# PM12_P1V8.net
KiCad netlist of a schematic drawn in Altium Designer
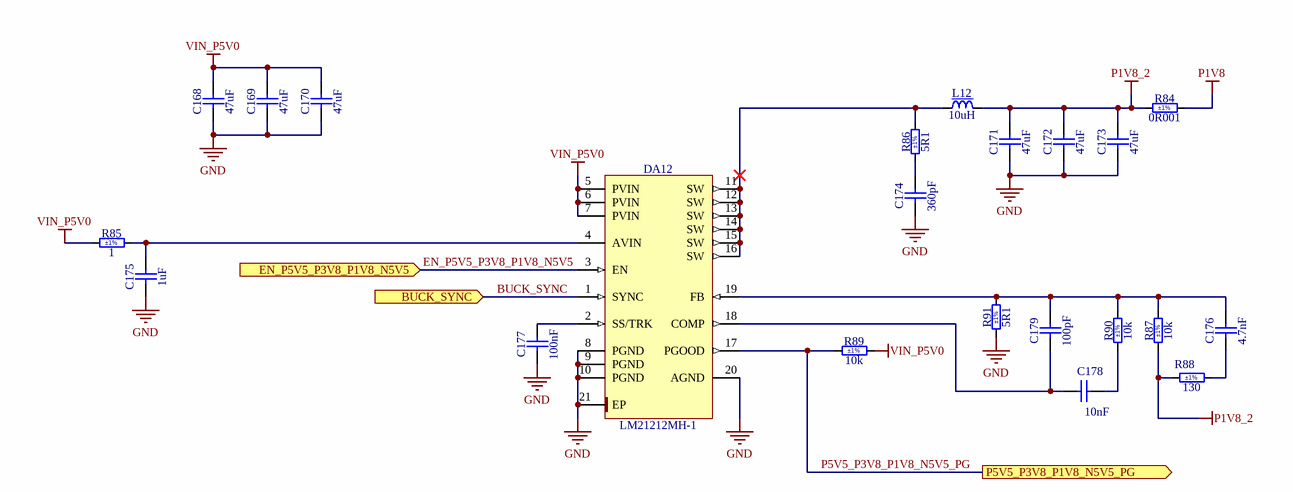
[diagram p0: PM12_P1V8.SchDoc]

(export (version "E")
  (design (tool "Eeschema 10.0.6"))
  (components
    (comp (ref "C168")
      (value "47uF")
      (footprint "CAPC3225X270N")
      (description "Non-polarised capacitor")
      (fields
        (field (name "PART NUMBER") "CC1210_47UF_16V_20%_X5R")
        (field (name "VOLTAGE") "16V")
        (field (name "AUTHOR") "CERN DEM MR")
      )
      (libsource (lib "Capacitors") (part "Capacitor - non polarized"))
    )
    (comp (ref "C169")
      (value "47uF")
      (footprint "CAPC3225X270N")
      (description "Non-polarised capacitor")
      (fields
        (field (name "PART NUMBER") "CC1210_47UF_16V_20%_X5R")
        (field (name "VOLTAGE") "16V")
        (field (name "AUTHOR") "CERN DEM MR")
      )
      (libsource (lib "Capacitors") (part "Capacitor - non polarized"))
    )
    (comp (ref "C170")
      (value "47uF")
      (footprint "CAPC3225X270N")
      (description "Non-polarised capacitor")
      (fields
        (field (name "PART NUMBER") "CC1210_47UF_16V_20%_X5R")
        (field (name "VOLTAGE") "16V")
        (field (name "AUTHOR") "CERN DEM MR")
      )
      (libsource (lib "Capacitors") (part "Capacitor - non polarized"))
    )
    (comp (ref "C171")
      (value "47uF")
      (footprint "CAPC3225X270N")
      (description "Non-polarised capacitor")
      (fields
        (field (name "PART NUMBER") "CC1210_47UF_16V_20%_X5R")
        (field (name "VOLTAGE") "16V")
        (field (name "AUTHOR") "CERN DEM MR")
      )
      (libsource (lib "Capacitors") (part "Capacitor - non polarized"))
    )
    (comp (ref "C172")
      (value "47uF")
      (footprint "CAPC3225X270N")
      (description "Non-polarised capacitor")
      (fields
        (field (name "PART NUMBER") "CC1210_47UF_16V_20%_X5R")
        (field (name "VOLTAGE") "16V")
        (field (name "AUTHOR") "CERN DEM MR")
      )
      (libsource (lib "Capacitors") (part "Capacitor - non polarized"))
    )
    (comp (ref "C173")
      (value "47uF")
      (footprint "CAPC3225X270N")
      (description "Non-polarised capacitor")
      (fields
        (field (name "PART NUMBER") "CC1210_47UF_16V_20%_X5R")
        (field (name "VOLTAGE") "16V")
        (field (name "AUTHOR") "CERN DEM MR")
      )
      (libsource (lib "Capacitors") (part "Capacitor - non polarized"))
    )
    (comp (ref "C174")
      (value "360pF")
      (footprint "CAPC2013X145N")
      (description "Non-polarised capacitor")
      (fields
        (field (name "PART NUMBER") "CC0805_360PF_50V_5%_C0G")
        (field (name "VOLTAGE") "50V")
        (field (name "AUTHOR") "CERN DEM HF")
      )
      (libsource (lib "Capacitors") (part "Capacitor - non polarized"))
    )
    (comp (ref "C175")
      (value "1uF")
      (footprint "CAPC2012X140N")
      (description "Non-polarised capacitor")
      (fields
        (field (name "PART NUMBER") "CC0805_1UF_25V_10%_X7R")
        (field (name "VOLTAGE") "25V")
        (field (name "AUTHOR") "CERN DEM JLC")
      )
      (libsource (lib "Capacitors") (part "Capacitor - non polarized"))
    )
    (comp (ref "C176")
      (value "4.7nF")
      (footprint "CAPC2012X135N")
      (description "Non-polarised capacitor")
      (fields
        (field (name "PART NUMBER") "CC0805_4.7NF_50V_10%_X7R")
        (field (name "VOLTAGE") "50V")
        (field (name "AUTHOR") "CERN DEM JLC")
      )
      (libsource (lib "Capacitors") (part "Capacitor - non polarized"))
    )
    (comp (ref "C177")
      (value "100nF")
      (footprint "CAPC2012X135N")
      (description "Non-polarised capacitor")
      (fields
        (field (name "PART NUMBER") "CC0805_100NF_50V_10%_X7R")
        (field (name "VOLTAGE") "50V")
        (field (name "AUTHOR") "CERN DEM JLC")
      )
      (libsource (lib "Capacitors") (part "Capacitor - non polarized"))
    )
    (comp (ref "C178")
      (value "10nF")
      (footprint "CAPC1005X55N")
      (description "Non-polarised capacitor")
      (fields
        (field (name "PART NUMBER") "CC0402_10NF_25V_10%_X7R")
        (field (name "VOLTAGE") "25V")
        (field (name "AUTHOR") "CERN DEM JLC")
      )
      (libsource (lib "Capacitors") (part "Capacitor - non polarized"))
    )
    (comp (ref "C179")
      (value "100pF")
      (footprint "CAPC2012X135N")
      (description "Non-polarised capacitor")
      (fields
        (field (name "PART NUMBER") "CC0805_100PF_50V_5%_NP0")
        (field (name "VOLTAGE") "50V")
        (field (name "AUTHOR") "CERN DEM JLC")
      )
      (libsource (lib "Capacitors") (part "Capacitor - non polarized"))
    )
    (comp (ref "DA12")
      (value "LM21212MH-1")
      (footprint "TEXAS_PWP0020AA")
      (description "2.95-V To 5.5-V, 12-A, Voltage-Mode Synchronous Buck Regulator with Frequency Synchronization")
      (fields (field (name "MANUFACTURER") "TEXAS INSTRUMENTS") (field (name "AUTHOR") "CERN DEM HF"))
      (libsource (lib "ICs And Semiconductors") (part "LM21212"))
    )
    (comp (ref "L12")
      (value "10uH")
      (footprint "IND_VISHAY_IHPL4040DZ-01")
      (description "Inductor With Core")
      (fields
        (field (name "PART NUMBER") "IND4040_10UH_20%_VISHAY_IHLP-4040DZ-01")
        (field (name "POWER") "6.8A")
        (field (name "AUTHOR") "CERN DEM HF")
      )
      (libsource (lib "Inductors & Transformers") (part "Inductor With Magnetic core"))
    )
    (comp (ref "R84")
      (value "0R001")
      (footprint "RESC_BOURNS_CRE2512_0R001-0R004")
      (description "Resistor - 1%")
      (fields
        (field (name "TOLERANCE") "±1%")
        (field (name "PART NUMBER") "R2512_0R001_1%_3W_50PPM_BOURNS_CRE2512")
        (field (name "POWER") "3W")
        (field (name "AUTHOR") "CERN DEM BC")
      )
      (libsource (lib "Resistors") (part "Resistor - 1%"))
    )
    (comp (ref "R85")
      (value "1")
      (footprint "RESC2012X60N")
      (description "Resistor - 1%")
      (fields
        (field (name "TOLERANCE") "±1%")
        (field (name "PART NUMBER") "R0805_1R_1%_0.125W_100PPM")
        (field (name "POWER") "0.125W")
        (field (name "AUTHOR") "CERN DEM HF")
      )
      (libsource (lib "Resistors") (part "Resistor - 1%"))
    )
    (comp (ref "R86")
      (value "5R1")
      (footprint "RESC2012X60N")
      (description "Resistor - 1%")
      (fields
        (field (name "TOLERANCE") "±1%")
        (field (name "PART NUMBER") "R0805_5R1_1%_0.125W_100PPM")
        (field (name "POWER") "0.125W")
        (field (name "AUTHOR") "CERN DEM HF")
      )
      (libsource (lib "Resistors") (part "Resistor - 1%"))
    )
    (comp (ref "R87")
      (value "10k")
      (footprint "RESC1608X55N")
      (description "Resistor - 1%")
      (fields
        (field (name "TOLERANCE") "±1%")
        (field (name "PART NUMBER") "R0603_10K_1%_0.1W_100PPM")
        (field (name "POWER") "0.1W")
        (field (name "AUTHOR") "CERN DEM JLC")
      )
      (libsource (lib "Resistors") (part "Resistor - 1%"))
    )
    (comp (ref "R88")
      (value "130")
      (footprint "RESC2012X60N")
      (description "Resistor - 1%")
      (fields
        (field (name "TOLERANCE") "±1%")
        (field (name "PART NUMBER") "R0805_130R_1%_0.125W_100PPM")
        (field (name "POWER") "0.125W")
        (field (name "AUTHOR") "CERN DEM JLC")
      )
      (libsource (lib "Resistors") (part "Resistor - 1%"))
    )
    (comp (ref "R89")
      (value "10k")
      (footprint "RESC1608X55N")
      (description "Resistor - 1%")
      (fields
        (field (name "TOLERANCE") "±1%")
        (field (name "PART NUMBER") "R0603_10K_1%_0.1W_100PPM")
        (field (name "POWER") "0.1W")
        (field (name "AUTHOR") "CERN DEM JLC")
      )
      (libsource (lib "Resistors") (part "Resistor - 1%"))
    )
    (comp (ref "R90")
      (value "10k")
      (footprint "RESC1608X55N")
      (description "Resistor - 1%")
      (fields
        (field (name "TOLERANCE") "±1%")
        (field (name "PART NUMBER") "R0603_10K_1%_0.1W_100PPM")
        (field (name "POWER") "0.1W")
        (field (name "AUTHOR") "CERN DEM JLC")
      )
      (libsource (lib "Resistors") (part "Resistor - 1%"))
    )
    (comp (ref "R91")
      (value "5R1")
      (footprint "RESC2012X60N")
      (description "Resistor - 1%")
      (fields
        (field (name "TOLERANCE") "±1%")
        (field (name "PART NUMBER") "R0805_5R1_1%_0.125W_100PPM")
        (field (name "POWER") "0.125W")
        (field (name "AUTHOR") "CERN DEM HF")
      )
      (libsource (lib "Resistors") (part "Resistor - 1%"))
    )
  )
  (nets
    (net (code "1") (name "/BUCK_SYNC") (class "Default")
      (node (ref "DA12") (pin "1") (pinfunction "SYNC_1") (pintype "input"))
    )
    (net (code "2") (name "/EN_P5V5_P3V8_P1V8_N5V5") (class "Default")
      (node (ref "DA12") (pin "3") (pinfunction "EN_3") (pintype "input"))
    )
    (net (code "3") (name "/P5V5_P3V8_P1V8_N5V5_PG") (class "Default")
      (node (ref "DA12") (pin "17") (pinfunction "PGOOD_17") (pintype "output"))
      (node (ref "R89") (pin "1") (pinfunction "1_1") (pintype "passive"))
    )
    (net (code "4") (name "GND") (class "Default")
      (node (ref "C168") (pin "1") (pinfunction "1_1") (pintype "passive"))
      (node (ref "C169") (pin "1") (pinfunction "1_1") (pintype "passive"))
      (node (ref "C170") (pin "1") (pinfunction "1_1") (pintype "passive"))
      (node (ref "C171") (pin "1") (pinfunction "1_1") (pintype "passive"))
      (node (ref "C172") (pin "1") (pinfunction "1_1") (pintype "passive"))
      (node (ref "C173") (pin "1") (pinfunction "1_1") (pintype "passive"))
      (node (ref "C174") (pin "1") (pinfunction "1_1") (pintype "passive"))
      (node (ref "C175") (pin "1") (pinfunction "1_1") (pintype "passive"))
      (node (ref "C177") (pin "1") (pinfunction "1_1") (pintype "passive"))
      (node (ref "DA12") (pin "10") (pinfunction "PGND_10") (pintype "power_in"))
      (node (ref "DA12") (pin "20") (pinfunction "AGND_20") (pintype "power_in"))
      (node (ref "DA12") (pin "21") (pinfunction "EP_21") (pintype "power_in"))
      (node (ref "DA12") (pin "8") (pinfunction "PGND_8") (pintype "power_in"))
      (node (ref "DA12") (pin "9") (pinfunction "PGND_9") (pintype "power_in"))
      (node (ref "R91") (pin "1") (pinfunction "1_1") (pintype "passive"))
    )
    (net (code "5") (name "Net-(C174-Pad2)") (class "Default")
      (node (ref "C174") (pin "2") (pinfunction "2_2") (pintype "passive"))
      (node (ref "R86") (pin "1") (pinfunction "1_1") (pintype "passive"))
    )
    (net (code "6") (name "Net-(C176-Pad1)") (class "Default")
      (node (ref "C176") (pin "1") (pinfunction "1_1") (pintype "passive"))
      (node (ref "R88") (pin "1") (pinfunction "1_1") (pintype "passive"))
    )
    (net (code "7") (name "Net-(C178-Pad1)") (class "Default")
      (node (ref "C178") (pin "1") (pinfunction "1_1") (pintype "passive"))
      (node (ref "R90") (pin "1") (pinfunction "1_1") (pintype "passive"))
    )
    (net (code "8") (name "Net-(DA12-AVIN)") (class "Default")
      (node (ref "C175") (pin "2") (pinfunction "2_2") (pintype "passive"))
      (node (ref "DA12") (pin "4") (pinfunction "AVIN_4") (pintype "power_in"))
      (node (ref "R85") (pin "2") (pinfunction "2_2") (pintype "passive"))
    )
    (net (code "9") (name "Net-(DA12-COMP)") (class "Default")
      (node (ref "C178") (pin "2") (pinfunction "2_2") (pintype "passive"))
      (node (ref "C179") (pin "1") (pinfunction "1_1") (pintype "passive"))
      (node (ref "DA12") (pin "18") (pinfunction "COMP_18") (pintype "output"))
    )
    (net (code "10") (name "Net-(DA12-FB)") (class "Default")
      (node (ref "C176") (pin "2") (pinfunction "2_2") (pintype "passive"))
      (node (ref "C179") (pin "2") (pinfunction "2_2") (pintype "passive"))
      (node (ref "DA12") (pin "19") (pinfunction "FB_19") (pintype "input"))
      (node (ref "R87") (pin "2") (pinfunction "2_2") (pintype "passive"))
      (node (ref "R90") (pin "2") (pinfunction "2_2") (pintype "passive"))
      (node (ref "R91") (pin "2") (pinfunction "2_2") (pintype "passive"))
    )
    (net (code "11") (name "Net-(DA12-SS{slash}TRK)") (class "Default")
      (node (ref "C177") (pin "2") (pinfunction "2_2") (pintype "passive"))
      (node (ref "DA12") (pin "2") (pinfunction "SS/TRK_2") (pintype "input"))
    )
    (net (code "12") (name "Net-(DA12-SW-Pad11)") (class "Default")
      (node (ref "DA12") (pin "11") (pinfunction "SW_11") (pintype "output"))
      (node (ref "DA12") (pin "12") (pinfunction "SW_12") (pintype "output"))
      (node (ref "DA12") (pin "13") (pinfunction "SW_13") (pintype "output"))
      (node (ref "DA12") (pin "14") (pinfunction "SW_14") (pintype "output"))
      (node (ref "DA12") (pin "15") (pinfunction "SW_15") (pintype "output"))
      (node (ref "DA12") (pin "16") (pinfunction "SW_16") (pintype "output"))
      (node (ref "L12") (pin "1") (pinfunction "1_1") (pintype "passive"))
      (node (ref "R86") (pin "2") (pinfunction "2_2") (pintype "passive"))
    )
    (net (code "13") (name "P1V8") (class "Default")
      (node (ref "R84") (pin "2") (pinfunction "2_2") (pintype "passive"))
    )
    (net (code "14") (name "P1V8_2") (class "Default")
      (node (ref "C171") (pin "2") (pinfunction "2_2") (pintype "passive"))
      (node (ref "C172") (pin "2") (pinfunction "2_2") (pintype "passive"))
      (node (ref "C173") (pin "2") (pinfunction "2_2") (pintype "passive"))
      (node (ref "L12") (pin "2") (pinfunction "2_2") (pintype "passive"))
      (node (ref "R84") (pin "1") (pinfunction "1_1") (pintype "passive"))
      (node (ref "R87") (pin "1") (pinfunction "1_1") (pintype "passive"))
      (node (ref "R88") (pin "2") (pinfunction "2_2") (pintype "passive"))
    )
    (net (code "15") (name "VIN_P5V0") (class "Default")
      (node (ref "C168") (pin "2") (pinfunction "2_2") (pintype "passive"))
      (node (ref "C169") (pin "2") (pinfunction "2_2") (pintype "passive"))
      (node (ref "C170") (pin "2") (pinfunction "2_2") (pintype "passive"))
      (node (ref "DA12") (pin "5") (pinfunction "PVIN_5") (pintype "power_in"))
      (node (ref "DA12") (pin "6") (pinfunction "PVIN_6") (pintype "power_in"))
      (node (ref "DA12") (pin "7") (pinfunction "PVIN_7") (pintype "power_in"))
      (node (ref "R85") (pin "1") (pinfunction "1_1") (pintype "passive"))
      (node (ref "R89") (pin "2") (pinfunction "2_2") (pintype "passive"))
    )
  )
)
